# Beagle_Cape.net
KiCad netlist of a schematic drawn in EAGLE
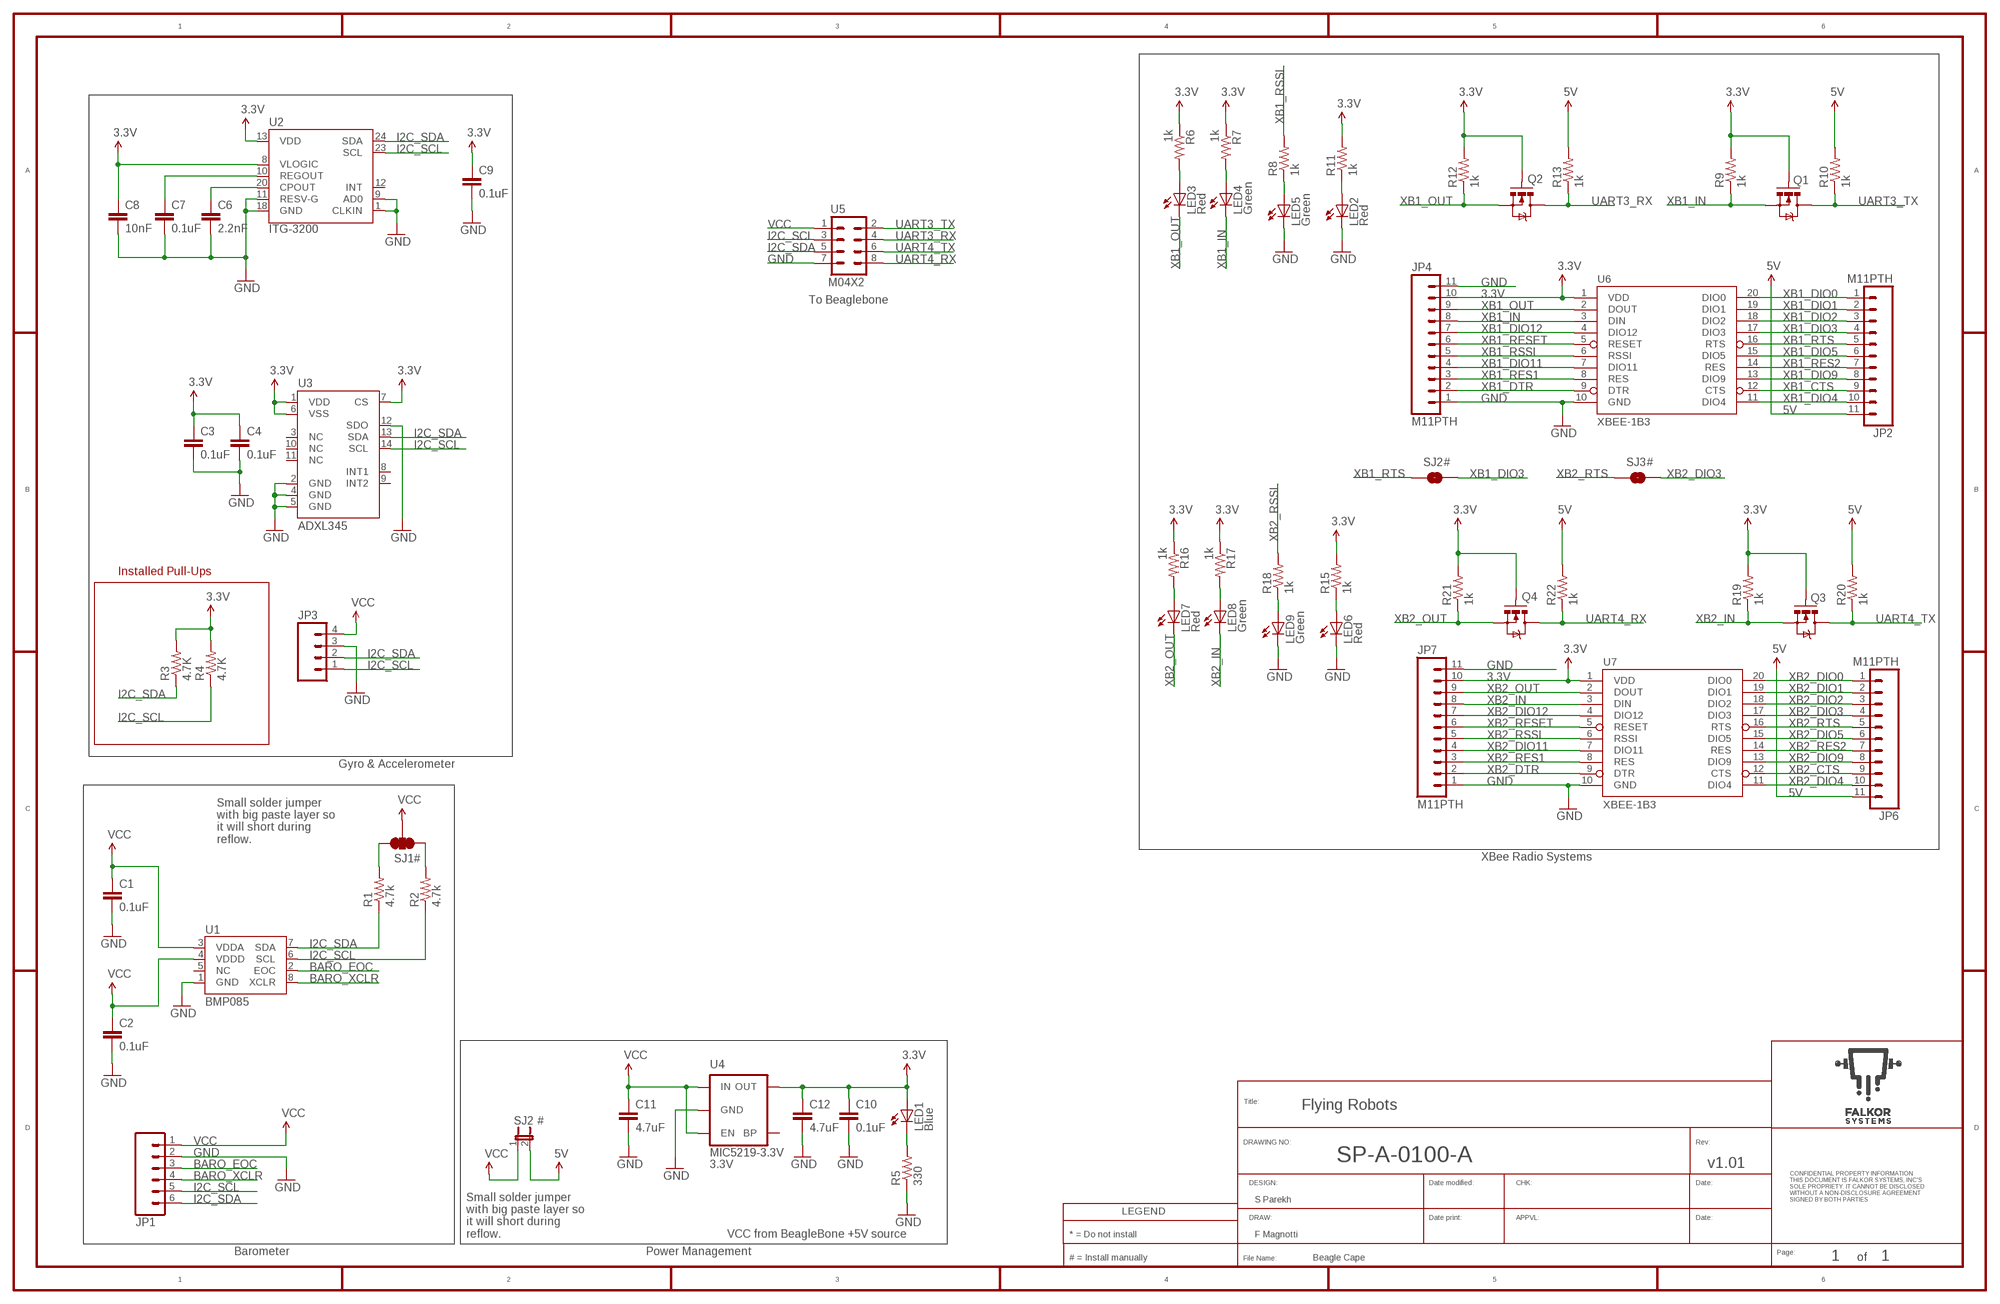
[diagram p0: schematic, sheet 1]

(export (version "E")
  (design (tool "Eeschema 10.0.6"))
  (components
    (comp (ref "C1")
      (value "0.1uF")
      (footprint "eagle-import:0402-CAP")
      (libsource (lib "eagle-import") (part "CAP0402-CAP"))
    )
    (comp (ref "C2")
      (value "0.1uF")
      (footprint "eagle-import:0402-CAP")
      (libsource (lib "eagle-import") (part "CAP0402-CAP"))
    )
    (comp (ref "C3")
      (value "0.1uF")
      (footprint "eagle-import:0402-CAP")
      (libsource (lib "eagle-import") (part "CAP0402-CAP"))
    )
    (comp (ref "C4")
      (value "0.1uF")
      (footprint "eagle-import:0402-CAP")
      (libsource (lib "eagle-import") (part "CAP0402-CAP"))
    )
    (comp (ref "C6")
      (value "2.2nF")
      (footprint "eagle-import:0402-CAP")
      (libsource (lib "eagle-import") (part "CAP0402-CAP"))
    )
    (comp (ref "C7")
      (value "0.1uF")
      (footprint "eagle-import:0402-CAP")
      (libsource (lib "eagle-import") (part "CAP0402-CAP"))
    )
    (comp (ref "C8")
      (value "10nF")
      (footprint "eagle-import:0402-CAP")
      (libsource (lib "eagle-import") (part "CAP0402-CAP"))
    )
    (comp (ref "C9")
      (value "0.1uF")
      (footprint "eagle-import:0402-CAP")
      (libsource (lib "eagle-import") (part "CAP0402-CAP"))
    )
    (comp (ref "C10")
      (value "0.1uF")
      (footprint "eagle-import:0402-CAP")
      (libsource (lib "eagle-import") (part "CAP0402-CAP"))
    )
    (comp (ref "C11")
      (value "4.7uF")
      (footprint "eagle-import:0402-CAP")
      (libsource (lib "eagle-import") (part "CAP0402-CAP"))
    )
    (comp (ref "C12")
      (value "4.7uF")
      (footprint "eagle-import:0402-CAP")
      (libsource (lib "eagle-import") (part "CAP0402-CAP"))
    )
    (comp (ref "JP1")
      (value "M06SIP")
      (footprint "eagle-import:1X06")
      (libsource (lib "eagle-import") (part "M06SIP"))
    )
    (comp (ref "JP2")
      (value "M11PTH")
      (footprint "eagle-import:1X11")
      (libsource (lib "eagle-import") (part "M11PTH"))
    )
    (comp (ref "JP3")
      (value "M04PTH")
      (footprint "eagle-import:1X04")
      (libsource (lib "eagle-import") (part "M04PTH"))
    )
    (comp (ref "JP4")
      (value "M11PTH")
      (footprint "eagle-import:1X11")
      (libsource (lib "eagle-import") (part "M11PTH"))
    )
    (comp (ref "JP6")
      (value "M11PTH")
      (footprint "eagle-import:1X11")
      (libsource (lib "eagle-import") (part "M11PTH"))
    )
    (comp (ref "JP7")
      (value "M11PTH")
      (footprint "eagle-import:1X11")
      (libsource (lib "eagle-import") (part "M11PTH"))
    )
    (comp (ref "LED1")
      (value "Blue")
      (footprint "eagle-import:LED-0603")
      (libsource (lib "eagle-import") (part "LED0603"))
    )
    (comp (ref "LED2")
      (value "Red")
      (footprint "eagle-import:LED-0603")
      (libsource (lib "eagle-import") (part "LED0603"))
    )
    (comp (ref "LED3")
      (value "Red")
      (footprint "eagle-import:LED-0603")
      (libsource (lib "eagle-import") (part "LED0603"))
    )
    (comp (ref "LED4")
      (value "Green")
      (footprint "eagle-import:LED-0603")
      (libsource (lib "eagle-import") (part "LED0603"))
    )
    (comp (ref "LED5")
      (value "Green")
      (footprint "eagle-import:LED-0603")
      (libsource (lib "eagle-import") (part "LED0603"))
    )
    (comp (ref "LED6")
      (value "Red")
      (footprint "eagle-import:LED-0603")
      (libsource (lib "eagle-import") (part "LED0603"))
    )
    (comp (ref "LED7")
      (value "Red")
      (footprint "eagle-import:LED-0603")
      (libsource (lib "eagle-import") (part "LED0603"))
    )
    (comp (ref "LED8")
      (value "Green")
      (footprint "eagle-import:LED-0603")
      (libsource (lib "eagle-import") (part "LED0603"))
    )
    (comp (ref "LED9")
      (value "Green")
      (footprint "eagle-import:LED-0603")
      (libsource (lib "eagle-import") (part "LED0603"))
    )
    (comp (ref "Q1")
      (value "MOSFET-NCHANNELSMD")
      (footprint "eagle-import:SOT23-3")
      (libsource (lib "eagle-import") (part "MOSFET-NCHANNELSMD"))
    )
    (comp (ref "Q2")
      (value "MOSFET-NCHANNELSMD")
      (footprint "eagle-import:SOT23-3")
      (libsource (lib "eagle-import") (part "MOSFET-NCHANNELSMD"))
    )
    (comp (ref "Q3")
      (value "MOSFET-NCHANNELSMD")
      (footprint "eagle-import:SOT23-3")
      (libsource (lib "eagle-import") (part "MOSFET-NCHANNELSMD"))
    )
    (comp (ref "Q4")
      (value "MOSFET-NCHANNELSMD")
      (footprint "eagle-import:SOT23-3")
      (libsource (lib "eagle-import") (part "MOSFET-NCHANNELSMD"))
    )
    (comp (ref "R1")
      (value "4.7k")
      (footprint "eagle-import:0402-RES")
      (libsource (lib "eagle-import") (part "RESISTOR0402-RES"))
    )
    (comp (ref "R2")
      (value "4.7k")
      (footprint "eagle-import:0402-RES")
      (libsource (lib "eagle-import") (part "RESISTOR0402-RES"))
    )
    (comp (ref "R3")
      (value "4.7K")
      (footprint "eagle-import:0402-RES")
      (libsource (lib "eagle-import") (part "RESISTOR0402-RES"))
    )
    (comp (ref "R4")
      (value "4.7K")
      (footprint "eagle-import:0402-RES")
      (libsource (lib "eagle-import") (part "RESISTOR0402-RES"))
    )
    (comp (ref "R5")
      (value "330")
      (footprint "eagle-import:0402-RES")
      (libsource (lib "eagle-import") (part "RESISTOR0402-RES"))
    )
    (comp (ref "R6")
      (value "1k")
      (footprint "eagle-import:0402-RES")
      (libsource (lib "eagle-import") (part "RESISTOR0402-RES"))
    )
    (comp (ref "R7")
      (value "1k")
      (footprint "eagle-import:0402-RES")
      (libsource (lib "eagle-import") (part "RESISTOR0402-RES"))
    )
    (comp (ref "R8")
      (value "1k")
      (footprint "eagle-import:0402-RES")
      (libsource (lib "eagle-import") (part "RESISTOR0402-RES"))
    )
    (comp (ref "R9")
      (value "1k")
      (footprint "eagle-import:0402-RES")
      (libsource (lib "eagle-import") (part "RESISTOR0402-RES"))
    )
    (comp (ref "R10")
      (value "1k")
      (footprint "eagle-import:0402-RES")
      (libsource (lib "eagle-import") (part "RESISTOR0402-RES"))
    )
    (comp (ref "R11")
      (value "1k")
      (footprint "eagle-import:0402-RES")
      (libsource (lib "eagle-import") (part "RESISTOR0402-RES"))
    )
    (comp (ref "R12")
      (value "1k")
      (footprint "eagle-import:0402-RES")
      (libsource (lib "eagle-import") (part "RESISTOR0402-RES"))
    )
    (comp (ref "R13")
      (value "1k")
      (footprint "eagle-import:0402-RES")
      (libsource (lib "eagle-import") (part "RESISTOR0402-RES"))
    )
    (comp (ref "R15")
      (value "1k")
      (footprint "eagle-import:0402-RES")
      (libsource (lib "eagle-import") (part "RESISTOR0402-RES"))
    )
    (comp (ref "R16")
      (value "1k")
      (footprint "eagle-import:0402-RES")
      (libsource (lib "eagle-import") (part "RESISTOR0402-RES"))
    )
    (comp (ref "R17")
      (value "1k")
      (footprint "eagle-import:0402-RES")
      (libsource (lib "eagle-import") (part "RESISTOR0402-RES"))
    )
    (comp (ref "R18")
      (value "1k")
      (footprint "eagle-import:0402-RES")
      (libsource (lib "eagle-import") (part "RESISTOR0402-RES"))
    )
    (comp (ref "R19")
      (value "1k")
      (footprint "eagle-import:0402-RES")
      (libsource (lib "eagle-import") (part "RESISTOR0402-RES"))
    )
    (comp (ref "R20")
      (value "1k")
      (footprint "eagle-import:0402-RES")
      (libsource (lib "eagle-import") (part "RESISTOR0402-RES"))
    )
    (comp (ref "R21")
      (value "1k")
      (footprint "eagle-import:0402-RES")
      (libsource (lib "eagle-import") (part "RESISTOR0402-RES"))
    )
    (comp (ref "R22")
      (value "1k")
      (footprint "eagle-import:0402-RES")
      (libsource (lib "eagle-import") (part "RESISTOR0402-RES"))
    )
    (comp (ref "SJ1")
      (value "SOLDERJUMPER_2WAYPASTE1&2&3")
      (footprint "eagle-import:SJ_3_PASTE1&2&3")
      (libsource (lib "eagle-import") (part "SOLDERJUMPER_2WAYPASTE1&2&3"))
    )
    (comp (ref "SJ2")
      (value "JUMPER-2SMD-NC")
      (footprint "eagle-import:SJ_2S")
      (libsource (lib "eagle-import") (part "JUMPER-2SMD-NC"))
    )
    (comp (ref "SJ2#")
      (value "SOLDERJUMPERNO")
      (footprint "eagle-import:SJ_2S-NO")
      (libsource (lib "eagle-import") (part "SOLDERJUMPERNO"))
    )
    (comp (ref "SJ3#")
      (value "SOLDERJUMPERNO")
      (footprint "eagle-import:SJ_2S-NO")
      (libsource (lib "eagle-import") (part "SOLDERJUMPERNO"))
    )
    (comp (ref "U1")
      (value "BMP085")
      (footprint "eagle-import:BMP085")
      (libsource (lib "eagle-import") (part "BMP085"))
    )
    (comp (ref "U2")
      (value "ITG-3200")
      (footprint "eagle-import:QFN-24")
      (libsource (lib "eagle-import") (part "ITG-3200"))
    )
    (comp (ref "U3")
      (value "ADXL345")
      (footprint "eagle-import:LGA14")
      (libsource (lib "eagle-import") (part "ADXL345"))
    )
    (comp (ref "U4")
      (value "3.3V")
      (footprint "eagle-import:SOT23-5")
      (libsource (lib "eagle-import") (part "V_REG_LDOSMD"))
    )
    (comp (ref "U5")
      (value "M04X2")
      (footprint "eagle-import:2X4")
      (libsource (lib "eagle-import") (part "M04X2"))
    )
    (comp (ref "U6")
      (value "XBEE-1B3")
      (footprint "eagle-import:XBEE-SMD")
      (libsource (lib "eagle-import") (part "XBEE-1B3"))
    )
    (comp (ref "U7")
      (value "XBEE-1B3")
      (footprint "eagle-import:XBEE-SMD")
      (libsource (lib "eagle-import") (part "XBEE-1B3"))
    )
  )
  (nets
    (net (code "1") (name "/BARO_EOC") (class "Default")
      (node (ref "JP1") (pin "3") (pinfunction "3_3") (pintype "passive"))
      (node (ref "U1") (pin "2") (pinfunction "EOC_2") (pintype "output"))
    )
    (net (code "2") (name "/BARO_XCLR") (class "Default")
      (node (ref "JP1") (pin "4") (pinfunction "4_4") (pintype "passive"))
      (node (ref "U1") (pin "8") (pinfunction "XCLR_8") (pintype "input"))
    )
    (net (code "3") (name "/I2C_SCL") (class "Default")
      (node (ref "JP1") (pin "5") (pinfunction "5_5") (pintype "passive"))
      (node (ref "JP3") (pin "1") (pinfunction "1_1") (pintype "passive"))
      (node (ref "R2") (pin "1") (pinfunction "1_1") (pintype "passive"))
      (node (ref "R4") (pin "1") (pinfunction "1_1") (pintype "passive"))
      (node (ref "U1") (pin "6") (pinfunction "SCL_6") (pintype "input"))
      (node (ref "U2") (pin "23") (pinfunction "SCL_23") (pintype "bidirectional"))
      (node (ref "U3") (pin "14") (pinfunction "SCL_14") (pintype "bidirectional"))
      (node (ref "U5") (pin "3") (pinfunction "3_3") (pintype "passive"))
    )
    (net (code "4") (name "/I2C_SDA") (class "Default")
      (node (ref "JP1") (pin "6") (pinfunction "6_6") (pintype "passive"))
      (node (ref "JP3") (pin "2") (pinfunction "2_2") (pintype "passive"))
      (node (ref "R1") (pin "1") (pinfunction "1_1") (pintype "passive"))
      (node (ref "R3") (pin "1") (pinfunction "1_1") (pintype "passive"))
      (node (ref "U1") (pin "7") (pinfunction "SDA_7") (pintype "bidirectional"))
      (node (ref "U2") (pin "24") (pinfunction "SDA_24") (pintype "bidirectional"))
      (node (ref "U3") (pin "13") (pinfunction "SDA_13") (pintype "bidirectional"))
      (node (ref "U5") (pin "5") (pinfunction "5_5") (pintype "passive"))
    )
    (net (code "5") (name "/UART3_RX") (class "Default")
      (node (ref "Q2") (pin "3") (pinfunction "D_3") (pintype "passive"))
      (node (ref "R13") (pin "1") (pinfunction "1_1") (pintype "passive"))
      (node (ref "U5") (pin "4") (pinfunction "4_4") (pintype "passive"))
    )
    (net (code "6") (name "/UART3_TX") (class "Default")
      (node (ref "Q1") (pin "3") (pinfunction "D_3") (pintype "passive"))
      (node (ref "R10") (pin "1") (pinfunction "1_1") (pintype "passive"))
      (node (ref "U5") (pin "2") (pinfunction "2_2") (pintype "passive"))
    )
    (net (code "7") (name "/UART4_RX") (class "Default")
      (node (ref "Q4") (pin "3") (pinfunction "D_3") (pintype "passive"))
      (node (ref "R22") (pin "1") (pinfunction "1_1") (pintype "passive"))
      (node (ref "U5") (pin "8") (pinfunction "8_8") (pintype "passive"))
    )
    (net (code "8") (name "/UART4_TX") (class "Default")
      (node (ref "Q3") (pin "3") (pinfunction "D_3") (pintype "passive"))
      (node (ref "R20") (pin "1") (pinfunction "1_1") (pintype "passive"))
      (node (ref "U5") (pin "6") (pinfunction "6_6") (pintype "passive"))
    )
    (net (code "9") (name "/XB1_CTS") (class "Default")
      (node (ref "JP2") (pin "9") (pinfunction "9_9") (pintype "passive"))
      (node (ref "U6") (pin "12") (pinfunction "CTS_12") (pintype "output"))
    )
    (net (code "10") (name "/XB1_DIO0") (class "Default")
      (node (ref "JP2") (pin "1") (pinfunction "1_1") (pintype "passive"))
      (node (ref "U6") (pin "20") (pinfunction "DIO0_20") (pintype "bidirectional"))
    )
    (net (code "11") (name "/XB1_DIO1") (class "Default")
      (node (ref "JP2") (pin "2") (pinfunction "2_2") (pintype "passive"))
      (node (ref "U6") (pin "19") (pinfunction "DIO1_19") (pintype "bidirectional"))
    )
    (net (code "12") (name "/XB1_DIO2") (class "Default")
      (node (ref "JP2") (pin "3") (pinfunction "3_3") (pintype "passive"))
      (node (ref "U6") (pin "18") (pinfunction "DIO2_18") (pintype "bidirectional"))
    )
    (net (code "13") (name "/XB1_DIO3") (class "Default")
      (node (ref "JP2") (pin "4") (pinfunction "4_4") (pintype "passive"))
      (node (ref "SJ2#") (pin "2") (pinfunction "2_2") (pintype "passive"))
      (node (ref "U6") (pin "17") (pinfunction "DIO3_17") (pintype "bidirectional"))
    )
    (net (code "14") (name "/XB1_DIO4") (class "Default")
      (node (ref "JP2") (pin "10") (pinfunction "10_10") (pintype "passive"))
      (node (ref "U6") (pin "11") (pinfunction "DIO4_11") (pintype "bidirectional"))
    )
    (net (code "15") (name "/XB1_DIO5") (class "Default")
      (node (ref "JP2") (pin "6") (pinfunction "6_6") (pintype "passive"))
      (node (ref "U6") (pin "15") (pinfunction "DIO5_15") (pintype "bidirectional"))
    )
    (net (code "16") (name "/XB1_DIO9") (class "Default")
      (node (ref "JP2") (pin "8") (pinfunction "8_8") (pintype "passive"))
      (node (ref "U6") (pin "13") (pinfunction "DIO9_13") (pintype "bidirectional"))
    )
    (net (code "17") (name "/XB1_DIO11") (class "Default")
      (node (ref "JP4") (pin "4") (pinfunction "4_4") (pintype "passive"))
      (node (ref "U6") (pin "7") (pinfunction "DIO11_7") (pintype "bidirectional"))
    )
    (net (code "18") (name "/XB1_DIO12") (class "Default")
      (node (ref "JP4") (pin "7") (pinfunction "7_7") (pintype "passive"))
      (node (ref "U6") (pin "4") (pinfunction "DIO12_4") (pintype "bidirectional"))
    )
    (net (code "19") (name "/XB1_DTR") (class "Default")
      (node (ref "JP4") (pin "2") (pinfunction "2_2") (pintype "passive"))
      (node (ref "U6") (pin "9") (pinfunction "DTR_9") (pintype "bidirectional"))
    )
    (net (code "20") (name "/XB1_IN") (class "Default")
      (node (ref "JP4") (pin "8") (pinfunction "8_8") (pintype "passive"))
      (node (ref "LED4") (pin "C") (pinfunction "C_C") (pintype "passive"))
      (node (ref "Q1") (pin "2") (pinfunction "S_2") (pintype "passive"))
      (node (ref "R9") (pin "1") (pinfunction "1_1") (pintype "passive"))
      (node (ref "U6") (pin "3") (pinfunction "DIN_3") (pintype "input"))
    )
    (net (code "21") (name "/XB1_OUT") (class "Default")
      (node (ref "JP4") (pin "9") (pinfunction "9_9") (pintype "passive"))
      (node (ref "LED3") (pin "C") (pinfunction "C_C") (pintype "passive"))
      (node (ref "Q2") (pin "2") (pinfunction "S_2") (pintype "passive"))
      (node (ref "R12") (pin "1") (pinfunction "1_1") (pintype "passive"))
      (node (ref "U6") (pin "2") (pinfunction "DOUT_2") (pintype "output"))
    )
    (net (code "22") (name "/XB1_RES1") (class "Default")
      (node (ref "JP4") (pin "3") (pinfunction "3_3") (pintype "passive"))
      (node (ref "U6") (pin "8") (pinfunction "RES_8") (pintype "bidirectional"))
    )
    (net (code "23") (name "/XB1_RES2") (class "Default")
      (node (ref "JP2") (pin "7") (pinfunction "7_7") (pintype "passive"))
      (node (ref "U6") (pin "14") (pinfunction "RES_14") (pintype "bidirectional"))
    )
    (net (code "24") (name "/XB1_RESET") (class "Default")
      (node (ref "JP4") (pin "6") (pinfunction "6_6") (pintype "passive"))
      (node (ref "U6") (pin "5") (pinfunction "RESET_5") (pintype "input"))
    )
    (net (code "25") (name "/XB1_RSSI") (class "Default")
      (node (ref "JP4") (pin "5") (pinfunction "5_5") (pintype "passive"))
      (node (ref "R8") (pin "2") (pinfunction "2_2") (pintype "passive"))
      (node (ref "U6") (pin "6") (pinfunction "RSSI_6") (pintype "bidirectional"))
    )
    (net (code "26") (name "/XB1_RTS") (class "Default")
      (node (ref "JP2") (pin "5") (pinfunction "5_5") (pintype "passive"))
      (node (ref "SJ2#") (pin "1") (pinfunction "1_1") (pintype "passive"))
      (node (ref "U6") (pin "16") (pinfunction "RTS_16") (pintype "input"))
    )
    (net (code "27") (name "/XB2_CTS") (class "Default")
      (node (ref "JP6") (pin "9") (pinfunction "9_9") (pintype "passive"))
      (node (ref "U7") (pin "12") (pinfunction "CTS_12") (pintype "output"))
    )
    (net (code "28") (name "/XB2_DIO0") (class "Default")
      (node (ref "JP6") (pin "1") (pinfunction "1_1") (pintype "passive"))
      (node (ref "U7") (pin "20") (pinfunction "DIO0_20") (pintype "bidirectional"))
    )
    (net (code "29") (name "/XB2_DIO1") (class "Default")
      (node (ref "JP6") (pin "2") (pinfunction "2_2") (pintype "passive"))
      (node (ref "U7") (pin "19") (pinfunction "DIO1_19") (pintype "bidirectional"))
    )
    (net (code "30") (name "/XB2_DIO2") (class "Default")
      (node (ref "JP6") (pin "3") (pinfunction "3_3") (pintype "passive"))
      (node (ref "U7") (pin "18") (pinfunction "DIO2_18") (pintype "bidirectional"))
    )
    (net (code "31") (name "/XB2_DIO3") (class "Default")
      (node (ref "JP6") (pin "4") (pinfunction "4_4") (pintype "passive"))
      (node (ref "SJ3#") (pin "2") (pinfunction "2_2") (pintype "passive"))
      (node (ref "U7") (pin "17") (pinfunction "DIO3_17") (pintype "bidirectional"))
    )
    (net (code "32") (name "/XB2_DIO4") (class "Default")
      (node (ref "JP6") (pin "10") (pinfunction "10_10") (pintype "passive"))
      (node (ref "U7") (pin "11") (pinfunction "DIO4_11") (pintype "bidirectional"))
    )
    (net (code "33") (name "/XB2_DIO5") (class "Default")
      (node (ref "JP6") (pin "6") (pinfunction "6_6") (pintype "passive"))
      (node (ref "U7") (pin "15") (pinfunction "DIO5_15") (pintype "bidirectional"))
    )
    (net (code "34") (name "/XB2_DIO9") (class "Default")
      (node (ref "JP6") (pin "8") (pinfunction "8_8") (pintype "passive"))
      (node (ref "U7") (pin "13") (pinfunction "DIO9_13") (pintype "bidirectional"))
    )
    (net (code "35") (name "/XB2_DIO11") (class "Default")
      (node (ref "JP7") (pin "4") (pinfunction "4_4") (pintype "passive"))
      (node (ref "U7") (pin "7") (pinfunction "DIO11_7") (pintype "bidirectional"))
    )
    (net (code "36") (name "/XB2_DIO12") (class "Default")
      (node (ref "JP7") (pin "7") (pinfunction "7_7") (pintype "passive"))
      (node (ref "U7") (pin "4") (pinfunction "DIO12_4") (pintype "bidirectional"))
    )
    (net (code "37") (name "/XB2_DTR") (class "Default")
      (node (ref "JP7") (pin "2") (pinfunction "2_2") (pintype "passive"))
      (node (ref "U7") (pin "9") (pinfunction "DTR_9") (pintype "bidirectional"))
    )
    (net (code "38") (name "/XB2_IN") (class "Default")
      (node (ref "JP7") (pin "8") (pinfunction "8_8") (pintype "passive"))
      (node (ref "LED8") (pin "C") (pinfunction "C_C") (pintype "passive"))
      (node (ref "Q3") (pin "2") (pinfunction "S_2") (pintype "passive"))
      (node (ref "R19") (pin "1") (pinfunction "1_1") (pintype "passive"))
      (node (ref "U7") (pin "3") (pinfunction "DIN_3") (pintype "input"))
    )
    (net (code "39") (name "/XB2_OUT") (class "Default")
      (node (ref "JP7") (pin "9") (pinfunction "9_9") (pintype "passive"))
      (node (ref "LED7") (pin "C") (pinfunction "C_C") (pintype "passive"))
      (node (ref "Q4") (pin "2") (pinfunction "S_2") (pintype "passive"))
      (node (ref "R21") (pin "1") (pinfunction "1_1") (pintype "passive"))
      (node (ref "U7") (pin "2") (pinfunction "DOUT_2") (pintype "output"))
    )
    (net (code "40") (name "/XB2_RES1") (class "Default")
      (node (ref "JP7") (pin "3") (pinfunction "3_3") (pintype "passive"))
      (node (ref "U7") (pin "8") (pinfunction "RES_8") (pintype "bidirectional"))
    )
    (net (code "41") (name "/XB2_RES2") (class "Default")
      (node (ref "JP6") (pin "7") (pinfunction "7_7") (pintype "passive"))
      (node (ref "U7") (pin "14") (pinfunction "RES_14") (pintype "bidirectional"))
    )
    (net (code "42") (name "/XB2_RESET") (class "Default")
      (node (ref "JP7") (pin "6") (pinfunction "6_6") (pintype "passive"))
      (node (ref "U7") (pin "5") (pinfunction "RESET_5") (pintype "input"))
    )
    (net (code "43") (name "/XB2_RSSI") (class "Default")
      (node (ref "JP7") (pin "5") (pinfunction "5_5") (pintype "passive"))
      (node (ref "R18") (pin "2") (pinfunction "2_2") (pintype "passive"))
      (node (ref "U7") (pin "6") (pinfunction "RSSI_6") (pintype "bidirectional"))
    )
    (net (code "44") (name "/XB2_RTS") (class "Default")
      (node (ref "JP6") (pin "5") (pinfunction "5_5") (pintype "passive"))
      (node (ref "SJ3#") (pin "1") (pinfunction "1_1") (pintype "passive"))
      (node (ref "U7") (pin "16") (pinfunction "RTS_16") (pintype "input"))
    )
    (net (code "45") (name "3.3V") (class "Default")
      (node (ref "C10") (pin "1") (pinfunction "1_1") (pintype "passive"))
      (node (ref "C12") (pin "1") (pinfunction "1_1") (pintype "passive"))
      (node (ref "C3") (pin "1") (pinfunction "1_1") (pintype "passive"))
      (node (ref "C4") (pin "1") (pinfunction "1_1") (pintype "passive"))
      (node (ref "C8") (pin "1") (pinfunction "1_1") (pintype "passive"))
      (node (ref "C9") (pin "1") (pinfunction "1_1") (pintype "passive"))
      (node (ref "JP4") (pin "10") (pinfunction "10_10") (pintype "passive"))
      (node (ref "JP7") (pin "10") (pinfunction "10_10") (pintype "passive"))
      (node (ref "LED1") (pin "A") (pinfunction "A_A") (pintype "passive"))
      (node (ref "Q1") (pin "1") (pinfunction "G_1") (pintype "passive"))
      (node (ref "Q2") (pin "1") (pinfunction "G_1") (pintype "passive"))
      (node (ref "Q3") (pin "1") (pinfunction "G_1") (pintype "passive"))
      (node (ref "Q4") (pin "1") (pinfunction "G_1") (pintype "passive"))
      (node (ref "R11") (pin "2") (pinfunction "2_2") (pintype "passive"))
      (node (ref "R12") (pin "2") (pinfunction "2_2") (pintype "passive"))
      (node (ref "R15") (pin "2") (pinfunction "2_2") (pintype "passive"))
      (node (ref "R16") (pin "1") (pinfunction "1_1") (pintype "passive"))
      (node (ref "R17") (pin "1") (pinfunction "1_1") (pintype "passive"))
      (node (ref "R19") (pin "2") (pinfunction "2_2") (pintype "passive"))
      (node (ref "R21") (pin "2") (pinfunction "2_2") (pintype "passive"))
      (node (ref "R3") (pin "2") (pinfunction "2_2") (pintype "passive"))
      (node (ref "R4") (pin "2") (pinfunction "2_2") (pintype "passive"))
      (node (ref "R6") (pin "1") (pinfunction "1_1") (pintype "passive"))
      (node (ref "R7") (pin "1") (pinfunction "1_1") (pintype "passive"))
      (node (ref "R9") (pin "2") (pinfunction "2_2") (pintype "passive"))
      (node (ref "U2") (pin "13") (pinfunction "VDD_13") (pintype "bidirectional"))
      (node (ref "U2") (pin "8") (pinfunction "VLOGIC_8") (pintype "bidirectional"))
      (node (ref "U3") (pin "1") (pinfunction "VDD_1") (pintype "bidirectional"))
      (node (ref "U3") (pin "6") (pinfunction "VSS_6") (pintype "bidirectional"))
      (node (ref "U3") (pin "7") (pinfunction "CS_7") (pintype "bidirectional"))
      (node (ref "U4") (pin "5") (pinfunction "OUT_5") (pintype "passive"))
      (node (ref "U6") (pin "1") (pinfunction "VDD_1") (pintype "power_in"))
      (node (ref "U7") (pin "1") (pinfunction "VDD_1") (pintype "power_in"))
    )
    (net (code "46") (name "5V") (class "Default")
      (node (ref "JP2") (pin "11") (pinfunction "11_11") (pintype "passive"))
      (node (ref "JP6") (pin "11") (pinfunction "11_11") (pintype "passive"))
      (node (ref "R10") (pin "2") (pinfunction "2_2") (pintype "passive"))
      (node (ref "R13") (pin "2") (pinfunction "2_2") (pintype "passive"))
      (node (ref "R20") (pin "2") (pinfunction "2_2") (pintype "passive"))
      (node (ref "R22") (pin "2") (pinfunction "2_2") (pintype "passive"))
      (node (ref "SJ2") (pin "2") (pinfunction "2_2") (pintype "passive"))
    )
    (net (code "47") (name "GND") (class "Default")
      (node (ref "C1") (pin "2") (pinfunction "2_2") (pintype "passive"))
      (node (ref "C10") (pin "2") (pinfunction "2_2") (pintype "passive"))
      (node (ref "C11") (pin "2") (pinfunction "2_2") (pintype "passive"))
      (node (ref "C12") (pin "2") (pinfunction "2_2") (pintype "passive"))
      (node (ref "C2") (pin "2") (pinfunction "2_2") (pintype "passive"))
      (node (ref "C3") (pin "2") (pinfunction "2_2") (pintype "passive"))
      (node (ref "C4") (pin "2") (pinfunction "2_2") (pintype "passive"))
      (node (ref "C6") (pin "2") (pinfunction "2_2") (pintype "passive"))
      (node (ref "C7") (pin "2") (pinfunction "2_2") (pintype "passive"))
      (node (ref "C8") (pin "2") (pinfunction "2_2") (pintype "passive"))
      (node (ref "C9") (pin "2") (pinfunction "2_2") (pintype "passive"))
      (node (ref "JP1") (pin "2") (pinfunction "2_2") (pintype "passive"))
      (node (ref "JP3") (pin "3") (pinfunction "3_3") (pintype "passive"))
      (node (ref "JP4") (pin "1") (pinfunction "1_1") (pintype "passive"))
      (node (ref "JP4") (pin "11") (pinfunction "11_11") (pintype "passive"))
      (node (ref "JP7") (pin "1") (pinfunction "1_1") (pintype "passive"))
      (node (ref "JP7") (pin "11") (pinfunction "11_11") (pintype "passive"))
      (node (ref "LED2") (pin "C") (pinfunction "C_C") (pintype "passive"))
      (node (ref "LED5") (pin "C") (pinfunction "C_C") (pintype "passive"))
      (node (ref "LED6") (pin "C") (pinfunction "C_C") (pintype "passive"))
      (node (ref "LED9") (pin "C") (pinfunction "C_C") (pintype "passive"))
      (node (ref "R5") (pin "1") (pinfunction "1_1") (pintype "passive"))
      (node (ref "U1") (pin "1") (pinfunction "GND_1") (pintype "power_in"))
      (node (ref "U2") (pin "1") (pinfunction "CLKIN_1") (pintype "bidirectional"))
      (node (ref "U2") (pin "11") (pinfunction "RESV-G_11") (pintype "bidirectional"))
      (node (ref "U2") (pin "18") (pinfunction "GND_18") (pintype "bidirectional"))
      (node (ref "U2") (pin "9") (pinfunction "AD0_9") (pintype "bidirectional"))
      (node (ref "U3") (pin "12") (pinfunction "SDO_12") (pintype "bidirectional"))
      (node (ref "U3") (pin "2") (pinfunction "GND_2") (pintype "bidirectional"))
      (node (ref "U3") (pin "4") (pinfunction "GND_4") (pintype "bidirectional"))
      (node (ref "U3") (pin "5") (pinfunction "GND_5") (pintype "bidirectional"))
      (node (ref "U4") (pin "2") (pinfunction "GND_2") (pintype "input"))
      (node (ref "U5") (pin "7") (pinfunction "7_7") (pintype "passive"))
      (node (ref "U6") (pin "10") (pinfunction "GND_10") (pintype "power_in"))
      (node (ref "U7") (pin "10") (pinfunction "GND_10") (pintype "power_in"))
    )
    (net (code "48") (name "Net-(LED1-PadC)") (class "Default")
      (node (ref "LED1") (pin "C") (pinfunction "C_C") (pintype "passive"))
      (node (ref "R5") (pin "2") (pinfunction "2_2") (pintype "passive"))
    )
    (net (code "49") (name "Net-(LED2-PadA)") (class "Default")
      (node (ref "LED2") (pin "A") (pinfunction "A_A") (pintype "passive"))
      (node (ref "R11") (pin "1") (pinfunction "1_1") (pintype "passive"))
    )
    (net (code "50") (name "Net-(LED3-PadA)") (class "Default")
      (node (ref "LED3") (pin "A") (pinfunction "A_A") (pintype "passive"))
      (node (ref "R6") (pin "2") (pinfunction "2_2") (pintype "passive"))
    )
    (net (code "51") (name "Net-(LED4-PadA)") (class "Default")
      (node (ref "LED4") (pin "A") (pinfunction "A_A") (pintype "passive"))
      (node (ref "R7") (pin "2") (pinfunction "2_2") (pintype "passive"))
    )
    (net (code "52") (name "Net-(LED5-PadA)") (class "Default")
      (node (ref "LED5") (pin "A") (pinfunction "A_A") (pintype "passive"))
      (node (ref "R8") (pin "1") (pinfunction "1_1") (pintype "passive"))
    )
    (net (code "53") (name "Net-(LED6-PadA)") (class "Default")
      (node (ref "LED6") (pin "A") (pinfunction "A_A") (pintype "passive"))
      (node (ref "R15") (pin "1") (pinfunction "1_1") (pintype "passive"))
    )
    (net (code "54") (name "Net-(LED7-PadA)") (class "Default")
      (node (ref "LED7") (pin "A") (pinfunction "A_A") (pintype "passive"))
      (node (ref "R16") (pin "2") (pinfunction "2_2") (pintype "passive"))
    )
    (net (code "55") (name "Net-(LED8-PadA)") (class "Default")
      (node (ref "LED8") (pin "A") (pinfunction "A_A") (pintype "passive"))
      (node (ref "R17") (pin "2") (pinfunction "2_2") (pintype "passive"))
    )
    (net (code "56") (name "Net-(LED9-PadA)") (class "Default")
      (node (ref "LED9") (pin "A") (pinfunction "A_A") (pintype "passive"))
      (node (ref "R18") (pin "1") (pinfunction "1_1") (pintype "passive"))
    )
    (net (code "57") (name "Net-(R1-Pad2)") (class "Default")
      (node (ref "R1") (pin "2") (pinfunction "2_2") (pintype "passive"))
      (node (ref "SJ1") (pin "3") (pinfunction "3_3") (pintype "passive"))
    )
    (net (code "58") (name "Net-(R2-Pad2)") (class "Default")
      (node (ref "R2") (pin "2") (pinfunction "2_2") (pintype "passive"))
      (node (ref "SJ1") (pin "1") (pinfunction "1_1") (pintype "passive"))
    )
    (net (code "59") (name "Net-(U2-CPOUT)") (class "Default")
      (node (ref "C6") (pin "1") (pinfunction "1_1") (pintype "passive"))
      (node (ref "U2") (pin "20") (pinfunction "CPOUT_20") (pintype "bidirectional"))
    )
    (net (code "60") (name "Net-(U2-REGOUT)") (class "Default")
      (node (ref "C7") (pin "1") (pinfunction "1_1") (pintype "passive"))
      (node (ref "U2") (pin "10") (pinfunction "REGOUT_10") (pintype "bidirectional"))
    )
    (net (code "61") (name "VCC") (class "Default")
      (node (ref "C1") (pin "1") (pinfunction "1_1") (pintype "passive"))
      (node (ref "C11") (pin "1") (pinfunction "1_1") (pintype "passive"))
      (node (ref "C2") (pin "1") (pinfunction "1_1") (pintype "passive"))
      (node (ref "JP1") (pin "1") (pinfunction "1_1") (pintype "passive"))
      (node (ref "JP3") (pin "4") (pinfunction "4_4") (pintype "passive"))
      (node (ref "SJ1") (pin "2") (pinfunction "2_2") (pintype "passive"))
      (node (ref "SJ2") (pin "1") (pinfunction "1_1") (pintype "passive"))
      (node (ref "U1") (pin "3") (pinfunction "VDDA_3") (pintype "power_in"))
      (node (ref "U1") (pin "4") (pinfunction "VDDD_4") (pintype "power_in"))
      (node (ref "U4") (pin "1") (pinfunction "IN_1") (pintype "input"))
      (node (ref "U4") (pin "3") (pinfunction "EN_3") (pintype "input"))
      (node (ref "U5") (pin "1") (pinfunction "1_1") (pintype "passive"))
    )
    (net (code "62") (name "unconnected-(U1-NC-Pad5)") (class "Default")
      (node (ref "U1") (pin "5") (pinfunction "NC_5") (pintype "bidirectional"))
    )
    (net (code "63") (name "unconnected-(U2-INT-Pad12)") (class "Default")
      (node (ref "U2") (pin "12") (pinfunction "INT_12") (pintype "bidirectional"))
    )
    (net (code "64") (name "unconnected-(U3-INT1-Pad8)") (class "Default")
      (node (ref "U3") (pin "8") (pinfunction "INT1_8") (pintype "bidirectional"))
    )
    (net (code "65") (name "unconnected-(U3-INT2-Pad9)") (class "Default")
      (node (ref "U3") (pin "9") (pinfunction "INT2_9") (pintype "bidirectional"))
    )
    (net (code "66") (name "unconnected-(U3-NC-Pad3)") (class "Default")
      (node (ref "U3") (pin "3") (pinfunction "NC_3") (pintype "bidirectional"))
    )
    (net (code "67") (name "unconnected-(U3-NC-Pad10)") (class "Default")
      (node (ref "U3") (pin "10") (pinfunction "NC_10") (pintype "bidirectional"))
    )
    (net (code "68") (name "unconnected-(U3-NC-Pad11)") (class "Default")
      (node (ref "U3") (pin "11") (pinfunction "NC_11") (pintype "bidirectional"))
    )
    (net (code "69") (name "unconnected-(U4-BP-Pad4)") (class "Default")
      (node (ref "U4") (pin "4") (pinfunction "BP_4") (pintype "input"))
    )
  )
)
